# 7_Segment_master.net
KiCad netlist of a schematic drawn in EAGLE
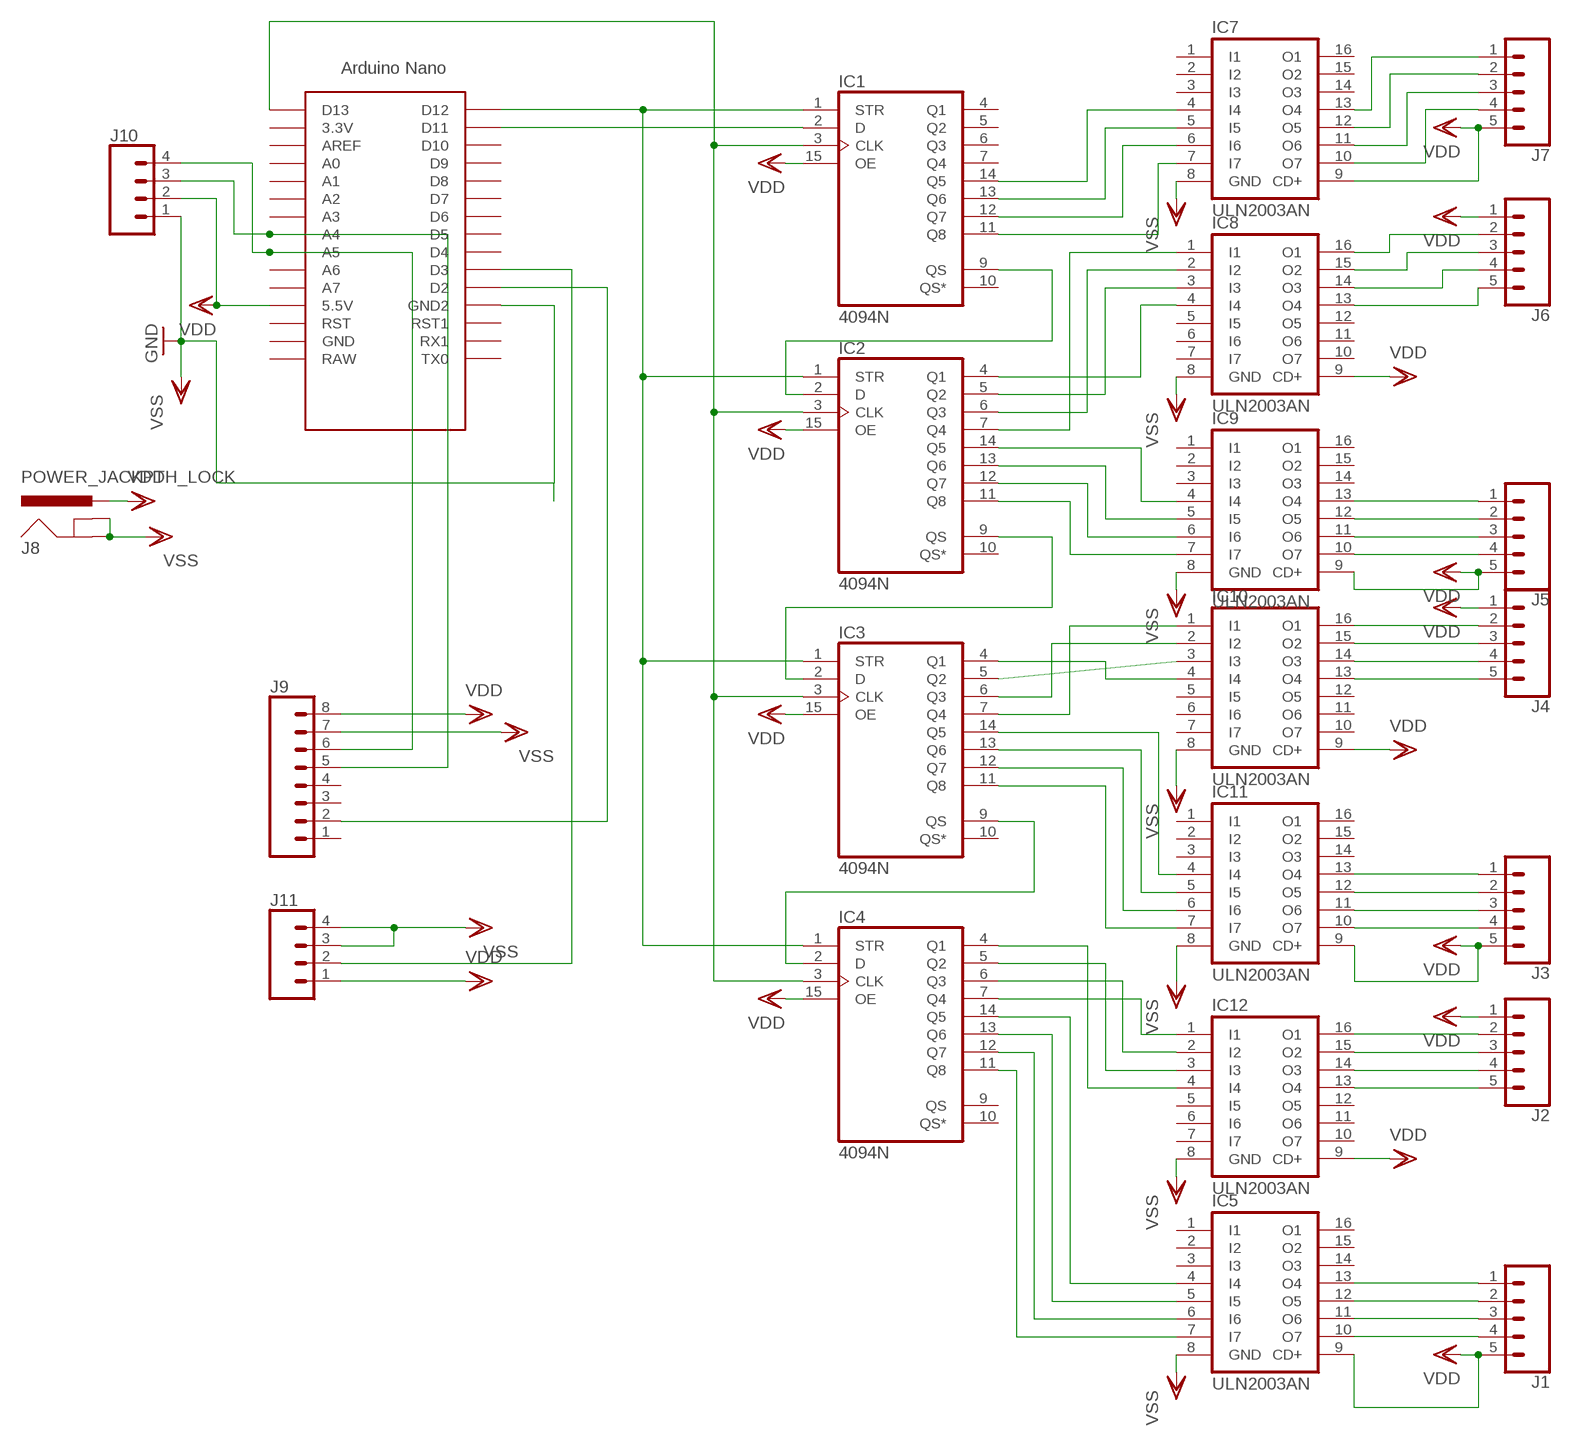
[diagram p0: schematic, sheet 1]

(export (version "E")
  (design (tool "Eeschema 10.0.6"))
  (components
    (comp (ref "IC1")
      (value "4094N")
      (footprint "eagle-import:DIL16")
      (libsource (lib "eagle-import") (part "4094N"))
    )
    (comp (ref "IC2")
      (value "4094N")
      (footprint "eagle-import:DIL16")
      (libsource (lib "eagle-import") (part "4094N"))
    )
    (comp (ref "IC3")
      (value "4094N")
      (footprint "eagle-import:DIL16")
      (libsource (lib "eagle-import") (part "4094N"))
    )
    (comp (ref "IC4")
      (value "4094N")
      (footprint "eagle-import:DIL16")
      (libsource (lib "eagle-import") (part "4094N"))
    )
    (comp (ref "IC5")
      (value "ULN2003AN")
      (footprint "eagle-import:DIL16")
      (libsource (lib "eagle-import") (part "ULN2003AN"))
    )
    (comp (ref "IC7")
      (value "ULN2003AN")
      (footprint "eagle-import:DIL16")
      (libsource (lib "eagle-import") (part "ULN2003AN"))
    )
    (comp (ref "IC8")
      (value "ULN2003AN")
      (footprint "eagle-import:DIL16")
      (libsource (lib "eagle-import") (part "ULN2003AN"))
    )
    (comp (ref "IC9")
      (value "ULN2003AN")
      (footprint "eagle-import:DIL16")
      (libsource (lib "eagle-import") (part "ULN2003AN"))
    )
    (comp (ref "IC10")
      (value "ULN2003AN")
      (footprint "eagle-import:DIL16")
      (libsource (lib "eagle-import") (part "ULN2003AN"))
    )
    (comp (ref "IC11")
      (value "ULN2003AN")
      (footprint "eagle-import:DIL16")
      (libsource (lib "eagle-import") (part "ULN2003AN"))
    )
    (comp (ref "IC12")
      (value "ULN2003AN")
      (footprint "eagle-import:DIL16")
      (libsource (lib "eagle-import") (part "ULN2003AN"))
    )
    (comp (ref "J1")
      (value "CONN_05LOCK_LONGPADS")
      (footprint "eagle-import:1X05_LOCK_LONGPADS")
      (libsource (lib "eagle-import") (part "CONN_05LOCK_LONGPADS"))
    )
    (comp (ref "J2")
      (value "CONN_05LOCK_LONGPADS")
      (footprint "eagle-import:1X05_LOCK_LONGPADS")
      (libsource (lib "eagle-import") (part "CONN_05LOCK_LONGPADS"))
    )
    (comp (ref "J3")
      (value "CONN_05LOCK_LONGPADS")
      (footprint "eagle-import:1X05_LOCK_LONGPADS")
      (libsource (lib "eagle-import") (part "CONN_05LOCK_LONGPADS"))
    )
    (comp (ref "J4")
      (value "CONN_05LOCK_LONGPADS")
      (footprint "eagle-import:1X05_LOCK_LONGPADS")
      (libsource (lib "eagle-import") (part "CONN_05LOCK_LONGPADS"))
    )
    (comp (ref "J5")
      (value "CONN_05LOCK_LONGPADS")
      (footprint "eagle-import:1X05_LOCK_LONGPADS")
      (libsource (lib "eagle-import") (part "CONN_05LOCK_LONGPADS"))
    )
    (comp (ref "J6")
      (value "CONN_05LOCK_LONGPADS")
      (footprint "eagle-import:1X05_LOCK_LONGPADS")
      (libsource (lib "eagle-import") (part "CONN_05LOCK_LONGPADS"))
    )
    (comp (ref "J7")
      (value "CONN_05LOCK_LONGPADS")
      (footprint "eagle-import:1X05_LOCK_LONGPADS")
      (libsource (lib "eagle-import") (part "CONN_05LOCK_LONGPADS"))
    )
    (comp (ref "J8")
      (value "POWER_JACKPTH_LOCK")
      (footprint "eagle-import:POWER_JACK_PTH_LOCK")
      (libsource (lib "eagle-import") (part "POWER_JACKPTH_LOCK"))
    )
    (comp (ref "J9")
      (value "CONN_08LOCK_LONGPADS")
      (footprint "eagle-import:1X08_LOCK_LONGPADS")
      (libsource (lib "eagle-import") (part "CONN_08LOCK_LONGPADS"))
    )
    (comp (ref "J10")
      (value "CONN_04")
      (footprint "eagle-import:SCREWTERMINAL-5MM-4")
      (libsource (lib "eagle-import") (part "CONN_04"))
    )
    (comp (ref "J11")
      (value "CONN_04LOCK_LONGPADS")
      (footprint "eagle-import:1X04_LOCK_LONGPADS")
      (libsource (lib "eagle-import") (part "CONN_04LOCK_LONGPADS"))
    )
    (comp (ref "U$1")
      (value "NANO")
      (footprint "eagle-import:NANO")
      (libsource (lib "eagle-import") (part "NANO"))
    )
  )
  (nets
    (net (code "1") (name "GND") (class "Default")
      (node (ref "IC10") (pin "8") (pinfunction "GND_8") (pintype "power_in"))
      (node (ref "IC11") (pin "8") (pinfunction "GND_8") (pintype "power_in"))
      (node (ref "IC12") (pin "8") (pinfunction "GND_8") (pintype "power_in"))
      (node (ref "IC5") (pin "8") (pinfunction "GND_8") (pintype "power_in"))
      (node (ref "IC7") (pin "8") (pinfunction "GND_8") (pintype "power_in"))
      (node (ref "IC8") (pin "8") (pinfunction "GND_8") (pintype "power_in"))
      (node (ref "IC9") (pin "8") (pinfunction "GND_8") (pintype "power_in"))
      (node (ref "J10") (pin "1") (pinfunction "1_1") (pintype "passive"))
      (node (ref "J11") (pin "3") (pinfunction "3_3") (pintype "passive"))
      (node (ref "J11") (pin "4") (pinfunction "4_4") (pintype "passive"))
      (node (ref "J8") (pin "GND") (pinfunction "GND_GND") (pintype "bidirectional"))
      (node (ref "J8") (pin "GNDBREAK") (pinfunction "GNDBREAK_GNDBREAK") (pintype "bidirectional"))
      (node (ref "J9") (pin "7") (pinfunction "7_7") (pintype "passive"))
      (node (ref "U$1") (pin "GND1") (pinfunction "GND2_GND1") (pintype "bidirectional"))
    )
    (net (code "2") (name "Net-(IC1A-CLK)") (class "Default")
      (node (ref "IC1") (pin "3") (pinfunction "CLK_3") (pintype "input"))
      (node (ref "IC2") (pin "3") (pinfunction "CLK_3") (pintype "input"))
      (node (ref "IC3") (pin "3") (pinfunction "CLK_3") (pintype "input"))
      (node (ref "IC4") (pin "3") (pinfunction "CLK_3") (pintype "input"))
      (node (ref "U$1") (pin "D13") (pinfunction "D13_D13") (pintype "bidirectional"))
    )
    (net (code "3") (name "Net-(IC1A-D)") (class "Default")
      (node (ref "IC1") (pin "2") (pinfunction "D_2") (pintype "input"))
      (node (ref "U$1") (pin "D11") (pinfunction "D11_D11") (pintype "bidirectional"))
    )
    (net (code "4") (name "Net-(IC1A-Q5)") (class "Default")
      (node (ref "IC1") (pin "14") (pinfunction "Q5_14") (pintype "output"))
      (node (ref "IC7") (pin "4") (pinfunction "I4_4") (pintype "input"))
    )
    (net (code "5") (name "Net-(IC1A-Q6)") (class "Default")
      (node (ref "IC1") (pin "13") (pinfunction "Q6_13") (pintype "output"))
      (node (ref "IC7") (pin "5") (pinfunction "I5_5") (pintype "input"))
    )
    (net (code "6") (name "Net-(IC1A-Q7)") (class "Default")
      (node (ref "IC1") (pin "12") (pinfunction "Q7_12") (pintype "output"))
      (node (ref "IC7") (pin "6") (pinfunction "I6_6") (pintype "input"))
    )
    (net (code "7") (name "Net-(IC1A-Q8)") (class "Default")
      (node (ref "IC1") (pin "11") (pinfunction "Q8_11") (pintype "output"))
      (node (ref "IC7") (pin "7") (pinfunction "I7_7") (pintype "input"))
    )
    (net (code "8") (name "Net-(IC1A-QS)") (class "Default")
      (node (ref "IC1") (pin "9") (pinfunction "QS_9") (pintype "output"))
      (node (ref "IC2") (pin "2") (pinfunction "D_2") (pintype "input"))
    )
    (net (code "9") (name "Net-(IC1A-STR)") (class "Default")
      (node (ref "IC1") (pin "1") (pinfunction "STR_1") (pintype "input"))
      (node (ref "IC2") (pin "1") (pinfunction "STR_1") (pintype "input"))
      (node (ref "IC3") (pin "1") (pinfunction "STR_1") (pintype "input"))
      (node (ref "IC4") (pin "1") (pinfunction "STR_1") (pintype "input"))
      (node (ref "U$1") (pin "D12") (pinfunction "D12_D12") (pintype "bidirectional"))
    )
    (net (code "10") (name "Net-(IC2A-Q1)") (class "Default")
      (node (ref "IC2") (pin "4") (pinfunction "Q1_4") (pintype "output"))
      (node (ref "IC8") (pin "4") (pinfunction "I4_4") (pintype "input"))
    )
    (net (code "11") (name "Net-(IC2A-Q2)") (class "Default")
      (node (ref "IC2") (pin "5") (pinfunction "Q2_5") (pintype "output"))
      (node (ref "IC8") (pin "3") (pinfunction "I3_3") (pintype "input"))
    )
    (net (code "12") (name "Net-(IC2A-Q3)") (class "Default")
      (node (ref "IC2") (pin "6") (pinfunction "Q3_6") (pintype "output"))
      (node (ref "IC8") (pin "2") (pinfunction "I2_2") (pintype "input"))
    )
    (net (code "13") (name "Net-(IC2A-Q4)") (class "Default")
      (node (ref "IC2") (pin "7") (pinfunction "Q4_7") (pintype "output"))
      (node (ref "IC8") (pin "1") (pinfunction "I1_1") (pintype "input"))
    )
    (net (code "14") (name "Net-(IC2A-Q5)") (class "Default")
      (node (ref "IC2") (pin "14") (pinfunction "Q5_14") (pintype "output"))
      (node (ref "IC9") (pin "4") (pinfunction "I4_4") (pintype "input"))
    )
    (net (code "15") (name "Net-(IC2A-Q6)") (class "Default")
      (node (ref "IC2") (pin "13") (pinfunction "Q6_13") (pintype "output"))
      (node (ref "IC9") (pin "5") (pinfunction "I5_5") (pintype "input"))
    )
    (net (code "16") (name "Net-(IC2A-Q7)") (class "Default")
      (node (ref "IC2") (pin "12") (pinfunction "Q7_12") (pintype "output"))
      (node (ref "IC9") (pin "6") (pinfunction "I6_6") (pintype "input"))
    )
    (net (code "17") (name "Net-(IC2A-Q8)") (class "Default")
      (node (ref "IC2") (pin "11") (pinfunction "Q8_11") (pintype "output"))
      (node (ref "IC9") (pin "7") (pinfunction "I7_7") (pintype "input"))
    )
    (net (code "18") (name "Net-(IC2A-QS)") (class "Default")
      (node (ref "IC2") (pin "9") (pinfunction "QS_9") (pintype "output"))
      (node (ref "IC3") (pin "2") (pinfunction "D_2") (pintype "input"))
    )
    (net (code "19") (name "Net-(IC3A-QS)") (class "Default")
      (node (ref "IC3") (pin "9") (pinfunction "QS_9") (pintype "output"))
      (node (ref "IC4") (pin "2") (pinfunction "D_2") (pintype "input"))
    )
    (net (code "20") (name "Net-(IC4A-Q5)") (class "Default")
      (node (ref "IC4") (pin "14") (pinfunction "Q5_14") (pintype "output"))
      (node (ref "IC5") (pin "4") (pinfunction "I4_4") (pintype "input"))
    )
    (net (code "21") (name "Net-(IC4A-Q6)") (class "Default")
      (node (ref "IC4") (pin "13") (pinfunction "Q6_13") (pintype "output"))
      (node (ref "IC5") (pin "5") (pinfunction "I5_5") (pintype "input"))
    )
    (net (code "22") (name "Net-(IC4A-Q7)") (class "Default")
      (node (ref "IC4") (pin "12") (pinfunction "Q7_12") (pintype "output"))
      (node (ref "IC5") (pin "6") (pinfunction "I6_6") (pintype "input"))
    )
    (net (code "23") (name "Net-(IC4A-Q8)") (class "Default")
      (node (ref "IC4") (pin "11") (pinfunction "Q8_11") (pintype "output"))
      (node (ref "IC5") (pin "7") (pinfunction "I7_7") (pintype "input"))
    )
    (net (code "24") (name "Net-(IC5-O4)") (class "Default")
      (node (ref "IC5") (pin "13") (pinfunction "O4_13") (pintype "open_collector"))
      (node (ref "J1") (pin "1") (pinfunction "1_1") (pintype "passive"))
    )
    (net (code "25") (name "Net-(IC5-O5)") (class "Default")
      (node (ref "IC5") (pin "12") (pinfunction "O5_12") (pintype "open_collector"))
      (node (ref "J1") (pin "2") (pinfunction "2_2") (pintype "passive"))
    )
    (net (code "26") (name "Net-(IC5-O6)") (class "Default")
      (node (ref "IC5") (pin "11") (pinfunction "O6_11") (pintype "open_collector"))
      (node (ref "J1") (pin "3") (pinfunction "3_3") (pintype "passive"))
    )
    (net (code "27") (name "Net-(IC5-O7)") (class "Default")
      (node (ref "IC5") (pin "10") (pinfunction "O7_10") (pintype "open_collector"))
      (node (ref "J1") (pin "4") (pinfunction "4_4") (pintype "passive"))
    )
    (net (code "28") (name "Net-(IC7-O4)") (class "Default")
      (node (ref "IC7") (pin "13") (pinfunction "O4_13") (pintype "open_collector"))
      (node (ref "J7") (pin "1") (pinfunction "1_1") (pintype "passive"))
    )
    (net (code "29") (name "Net-(IC7-O5)") (class "Default")
      (node (ref "IC7") (pin "12") (pinfunction "O5_12") (pintype "open_collector"))
      (node (ref "J7") (pin "2") (pinfunction "2_2") (pintype "passive"))
    )
    (net (code "30") (name "Net-(IC7-O6)") (class "Default")
      (node (ref "IC7") (pin "11") (pinfunction "O6_11") (pintype "open_collector"))
      (node (ref "J7") (pin "3") (pinfunction "3_3") (pintype "passive"))
    )
    (net (code "31") (name "Net-(IC7-O7)") (class "Default")
      (node (ref "IC7") (pin "10") (pinfunction "O7_10") (pintype "open_collector"))
      (node (ref "J7") (pin "4") (pinfunction "4_4") (pintype "passive"))
    )
    (net (code "32") (name "Net-(IC8-O1)") (class "Default")
      (node (ref "IC8") (pin "16") (pinfunction "O1_16") (pintype "open_collector"))
      (node (ref "J6") (pin "2") (pinfunction "2_2") (pintype "passive"))
    )
    (net (code "33") (name "Net-(IC8-O2)") (class "Default")
      (node (ref "IC8") (pin "15") (pinfunction "O2_15") (pintype "open_collector"))
      (node (ref "J6") (pin "3") (pinfunction "3_3") (pintype "passive"))
    )
    (net (code "34") (name "Net-(IC8-O3)") (class "Default")
      (node (ref "IC8") (pin "14") (pinfunction "O3_14") (pintype "open_collector"))
      (node (ref "J6") (pin "4") (pinfunction "4_4") (pintype "passive"))
    )
    (net (code "35") (name "Net-(IC8-O4)") (class "Default")
      (node (ref "IC8") (pin "13") (pinfunction "O4_13") (pintype "open_collector"))
      (node (ref "J6") (pin "5") (pinfunction "5_5") (pintype "passive"))
    )
    (net (code "36") (name "Net-(IC9-O4)") (class "Default")
      (node (ref "IC9") (pin "13") (pinfunction "O4_13") (pintype "open_collector"))
      (node (ref "J5") (pin "1") (pinfunction "1_1") (pintype "passive"))
    )
    (net (code "37") (name "Net-(IC9-O5)") (class "Default")
      (node (ref "IC9") (pin "12") (pinfunction "O5_12") (pintype "open_collector"))
      (node (ref "J5") (pin "2") (pinfunction "2_2") (pintype "passive"))
    )
    (net (code "38") (name "Net-(IC9-O6)") (class "Default")
      (node (ref "IC9") (pin "11") (pinfunction "O6_11") (pintype "open_collector"))
      (node (ref "J5") (pin "3") (pinfunction "3_3") (pintype "passive"))
    )
    (net (code "39") (name "Net-(IC9-O7)") (class "Default")
      (node (ref "IC9") (pin "10") (pinfunction "O7_10") (pintype "open_collector"))
      (node (ref "J5") (pin "4") (pinfunction "4_4") (pintype "passive"))
    )
    (net (code "40") (name "Net-(IC10-I1)") (class "Default")
      (node (ref "IC10") (pin "1") (pinfunction "I1_1") (pintype "input"))
      (node (ref "IC3") (pin "7") (pinfunction "Q4_7") (pintype "output"))
    )
    (net (code "41") (name "Net-(IC10-I2)") (class "Default")
      (node (ref "IC10") (pin "2") (pinfunction "I2_2") (pintype "input"))
      (node (ref "IC3") (pin "6") (pinfunction "Q3_6") (pintype "output"))
    )
    (net (code "42") (name "Net-(IC10-I3)") (class "Default")
      (node (ref "IC10") (pin "3") (pinfunction "I3_3") (pintype "input"))
      (node (ref "IC3") (pin "5") (pinfunction "Q2_5") (pintype "output"))
    )
    (net (code "43") (name "Net-(IC10-I4)") (class "Default")
      (node (ref "IC10") (pin "4") (pinfunction "I4_4") (pintype "input"))
      (node (ref "IC3") (pin "4") (pinfunction "Q1_4") (pintype "output"))
    )
    (net (code "44") (name "Net-(IC10-O1)") (class "Default")
      (node (ref "IC10") (pin "16") (pinfunction "O1_16") (pintype "open_collector"))
      (node (ref "J4") (pin "2") (pinfunction "2_2") (pintype "passive"))
    )
    (net (code "45") (name "Net-(IC10-O2)") (class "Default")
      (node (ref "IC10") (pin "15") (pinfunction "O2_15") (pintype "open_collector"))
      (node (ref "J4") (pin "3") (pinfunction "3_3") (pintype "passive"))
    )
    (net (code "46") (name "Net-(IC10-O3)") (class "Default")
      (node (ref "IC10") (pin "14") (pinfunction "O3_14") (pintype "open_collector"))
      (node (ref "J4") (pin "4") (pinfunction "4_4") (pintype "passive"))
    )
    (net (code "47") (name "Net-(IC10-O4)") (class "Default")
      (node (ref "IC10") (pin "13") (pinfunction "O4_13") (pintype "open_collector"))
      (node (ref "J4") (pin "5") (pinfunction "5_5") (pintype "passive"))
    )
    (net (code "48") (name "Net-(IC11-I4)") (class "Default")
      (node (ref "IC11") (pin "4") (pinfunction "I4_4") (pintype "input"))
      (node (ref "IC3") (pin "14") (pinfunction "Q5_14") (pintype "output"))
    )
    (net (code "49") (name "Net-(IC11-I5)") (class "Default")
      (node (ref "IC11") (pin "5") (pinfunction "I5_5") (pintype "input"))
      (node (ref "IC3") (pin "13") (pinfunction "Q6_13") (pintype "output"))
    )
    (net (code "50") (name "Net-(IC11-I6)") (class "Default")
      (node (ref "IC11") (pin "6") (pinfunction "I6_6") (pintype "input"))
      (node (ref "IC3") (pin "12") (pinfunction "Q7_12") (pintype "output"))
    )
    (net (code "51") (name "Net-(IC11-I7)") (class "Default")
      (node (ref "IC11") (pin "7") (pinfunction "I7_7") (pintype "input"))
      (node (ref "IC3") (pin "11") (pinfunction "Q8_11") (pintype "output"))
    )
    (net (code "52") (name "Net-(IC11-O4)") (class "Default")
      (node (ref "IC11") (pin "13") (pinfunction "O4_13") (pintype "open_collector"))
      (node (ref "J3") (pin "1") (pinfunction "1_1") (pintype "passive"))
    )
    (net (code "53") (name "Net-(IC11-O5)") (class "Default")
      (node (ref "IC11") (pin "12") (pinfunction "O5_12") (pintype "open_collector"))
      (node (ref "J3") (pin "2") (pinfunction "2_2") (pintype "passive"))
    )
    (net (code "54") (name "Net-(IC11-O6)") (class "Default")
      (node (ref "IC11") (pin "11") (pinfunction "O6_11") (pintype "open_collector"))
      (node (ref "J3") (pin "3") (pinfunction "3_3") (pintype "passive"))
    )
    (net (code "55") (name "Net-(IC11-O7)") (class "Default")
      (node (ref "IC11") (pin "10") (pinfunction "O7_10") (pintype "open_collector"))
      (node (ref "J3") (pin "4") (pinfunction "4_4") (pintype "passive"))
    )
    (net (code "56") (name "Net-(IC12-I1)") (class "Default")
      (node (ref "IC12") (pin "1") (pinfunction "I1_1") (pintype "input"))
      (node (ref "IC4") (pin "7") (pinfunction "Q4_7") (pintype "output"))
    )
    (net (code "57") (name "Net-(IC12-I2)") (class "Default")
      (node (ref "IC12") (pin "2") (pinfunction "I2_2") (pintype "input"))
      (node (ref "IC4") (pin "6") (pinfunction "Q3_6") (pintype "output"))
    )
    (net (code "58") (name "Net-(IC12-I3)") (class "Default")
      (node (ref "IC12") (pin "3") (pinfunction "I3_3") (pintype "input"))
      (node (ref "IC4") (pin "5") (pinfunction "Q2_5") (pintype "output"))
    )
    (net (code "59") (name "Net-(IC12-I4)") (class "Default")
      (node (ref "IC12") (pin "4") (pinfunction "I4_4") (pintype "input"))
      (node (ref "IC4") (pin "4") (pinfunction "Q1_4") (pintype "output"))
    )
    (net (code "60") (name "Net-(IC12-O1)") (class "Default")
      (node (ref "IC12") (pin "16") (pinfunction "O1_16") (pintype "open_collector"))
      (node (ref "J2") (pin "2") (pinfunction "2_2") (pintype "passive"))
    )
    (net (code "61") (name "Net-(IC12-O2)") (class "Default")
      (node (ref "IC12") (pin "15") (pinfunction "O2_15") (pintype "open_collector"))
      (node (ref "J2") (pin "3") (pinfunction "3_3") (pintype "passive"))
    )
    (net (code "62") (name "Net-(IC12-O3)") (class "Default")
      (node (ref "IC12") (pin "14") (pinfunction "O3_14") (pintype "open_collector"))
      (node (ref "J2") (pin "4") (pinfunction "4_4") (pintype "passive"))
    )
    (net (code "63") (name "Net-(IC12-O4)") (class "Default")
      (node (ref "IC12") (pin "13") (pinfunction "O4_13") (pintype "open_collector"))
      (node (ref "J2") (pin "5") (pinfunction "5_5") (pintype "passive"))
    )
    (net (code "64") (name "Net-(J9-Pad2)") (class "Default")
      (node (ref "J9") (pin "2") (pinfunction "2_2") (pintype "passive"))
      (node (ref "U$1") (pin "D2") (pinfunction "D2_D2") (pintype "bidirectional"))
    )
    (net (code "65") (name "Net-(J10-Pad3)") (class "Default")
      (node (ref "J10") (pin "3") (pinfunction "3_3") (pintype "passive"))
      (node (ref "J9") (pin "5") (pinfunction "5_5") (pintype "passive"))
      (node (ref "U$1") (pin "A4") (pinfunction "A4_A4") (pintype "bidirectional"))
    )
    (net (code "66") (name "Net-(J10-Pad4)") (class "Default")
      (node (ref "J10") (pin "4") (pinfunction "4_4") (pintype "passive"))
      (node (ref "J9") (pin "6") (pinfunction "6_6") (pintype "passive"))
      (node (ref "U$1") (pin "A5") (pinfunction "A5_A5") (pintype "bidirectional"))
    )
    (net (code "67") (name "Net-(J11-Pad2)") (class "Default")
      (node (ref "J11") (pin "2") (pinfunction "2_2") (pintype "passive"))
      (node (ref "U$1") (pin "D3") (pinfunction "D3_D3") (pintype "bidirectional"))
    )
    (net (code "68") (name "VDD") (class "Default")
      (node (ref "IC1") (pin "15") (pinfunction "OE_15") (pintype "input"))
      (node (ref "IC10") (pin "9") (pinfunction "CD+_9") (pintype "passive"))
      (node (ref "IC11") (pin "9") (pinfunction "CD+_9") (pintype "passive"))
      (node (ref "IC12") (pin "9") (pinfunction "CD+_9") (pintype "passive"))
      (node (ref "IC2") (pin "15") (pinfunction "OE_15") (pintype "input"))
      (node (ref "IC3") (pin "15") (pinfunction "OE_15") (pintype "input"))
      (node (ref "IC4") (pin "15") (pinfunction "OE_15") (pintype "input"))
      (node (ref "IC5") (pin "9") (pinfunction "CD+_9") (pintype "passive"))
      (node (ref "IC7") (pin "9") (pinfunction "CD+_9") (pintype "passive"))
      (node (ref "IC8") (pin "9") (pinfunction "CD+_9") (pintype "passive"))
      (node (ref "IC9") (pin "9") (pinfunction "CD+_9") (pintype "passive"))
      (node (ref "J1") (pin "5") (pinfunction "5_5") (pintype "passive"))
      (node (ref "J10") (pin "2") (pinfunction "2_2") (pintype "passive"))
      (node (ref "J11") (pin "1") (pinfunction "1_1") (pintype "passive"))
      (node (ref "J2") (pin "1") (pinfunction "1_1") (pintype "passive"))
      (node (ref "J3") (pin "5") (pinfunction "5_5") (pintype "passive"))
      (node (ref "J4") (pin "1") (pinfunction "1_1") (pintype "passive"))
      (node (ref "J5") (pin "5") (pinfunction "5_5") (pintype "passive"))
      (node (ref "J6") (pin "1") (pinfunction "1_1") (pintype "passive"))
      (node (ref "J7") (pin "5") (pinfunction "5_5") (pintype "passive"))
      (node (ref "J8") (pin "PWR") (pinfunction "PWR_PWR") (pintype "bidirectional"))
      (node (ref "J9") (pin "8") (pinfunction "8_8") (pintype "passive"))
      (node (ref "U$1") (pin "5V") (pinfunction "5.5V_5V") (pintype "bidirectional"))
    )
    (net (code "69") (name "unconnected-(IC1A-Q1-Pad4)") (class "Default")
      (node (ref "IC1") (pin "4") (pinfunction "Q1_4") (pintype "output"))
    )
    (net (code "70") (name "unconnected-(IC1A-Q2-Pad5)") (class "Default")
      (node (ref "IC1") (pin "5") (pinfunction "Q2_5") (pintype "output"))
    )
    (net (code "71") (name "unconnected-(IC1A-Q3-Pad6)") (class "Default")
      (node (ref "IC1") (pin "6") (pinfunction "Q3_6") (pintype "output"))
    )
    (net (code "72") (name "unconnected-(IC1A-Q4-Pad7)") (class "Default")
      (node (ref "IC1") (pin "7") (pinfunction "Q4_7") (pintype "output"))
    )
    (net (code "73") (name "unconnected-(IC1A-QS*-Pad10)") (class "Default")
      (node (ref "IC1") (pin "10") (pinfunction "QS*_10") (pintype "output"))
    )
    (net (code "74") (name "unconnected-(IC2A-QS*-Pad10)") (class "Default")
      (node (ref "IC2") (pin "10") (pinfunction "QS*_10") (pintype "output"))
    )
    (net (code "75") (name "unconnected-(IC3A-QS*-Pad10)") (class "Default")
      (node (ref "IC3") (pin "10") (pinfunction "QS*_10") (pintype "output"))
    )
    (net (code "76") (name "unconnected-(IC4A-QS*-Pad10)") (class "Default")
      (node (ref "IC4") (pin "10") (pinfunction "QS*_10") (pintype "output"))
    )
    (net (code "77") (name "unconnected-(IC4A-QS-Pad9)") (class "Default")
      (node (ref "IC4") (pin "9") (pinfunction "QS_9") (pintype "output"))
    )
    (net (code "78") (name "unconnected-(IC5-I1-Pad1)") (class "Default")
      (node (ref "IC5") (pin "1") (pinfunction "I1_1") (pintype "input"))
    )
    (net (code "79") (name "unconnected-(IC5-I2-Pad2)") (class "Default")
      (node (ref "IC5") (pin "2") (pinfunction "I2_2") (pintype "input"))
    )
    (net (code "80") (name "unconnected-(IC5-I3-Pad3)") (class "Default")
      (node (ref "IC5") (pin "3") (pinfunction "I3_3") (pintype "input"))
    )
    (net (code "81") (name "unconnected-(IC5-O1-Pad16)") (class "Default")
      (node (ref "IC5") (pin "16") (pinfunction "O1_16") (pintype "open_collector"))
    )
    (net (code "82") (name "unconnected-(IC5-O2-Pad15)") (class "Default")
      (node (ref "IC5") (pin "15") (pinfunction "O2_15") (pintype "open_collector"))
    )
    (net (code "83") (name "unconnected-(IC5-O3-Pad14)") (class "Default")
      (node (ref "IC5") (pin "14") (pinfunction "O3_14") (pintype "open_collector"))
    )
    (net (code "84") (name "unconnected-(IC7-I1-Pad1)") (class "Default")
      (node (ref "IC7") (pin "1") (pinfunction "I1_1") (pintype "input"))
    )
    (net (code "85") (name "unconnected-(IC7-I2-Pad2)") (class "Default")
      (node (ref "IC7") (pin "2") (pinfunction "I2_2") (pintype "input"))
    )
    (net (code "86") (name "unconnected-(IC7-I3-Pad3)") (class "Default")
      (node (ref "IC7") (pin "3") (pinfunction "I3_3") (pintype "input"))
    )
    (net (code "87") (name "unconnected-(IC7-O1-Pad16)") (class "Default")
      (node (ref "IC7") (pin "16") (pinfunction "O1_16") (pintype "open_collector"))
    )
    (net (code "88") (name "unconnected-(IC7-O2-Pad15)") (class "Default")
      (node (ref "IC7") (pin "15") (pinfunction "O2_15") (pintype "open_collector"))
    )
    (net (code "89") (name "unconnected-(IC7-O3-Pad14)") (class "Default")
      (node (ref "IC7") (pin "14") (pinfunction "O3_14") (pintype "open_collector"))
    )
    (net (code "90") (name "unconnected-(IC8-I5-Pad5)") (class "Default")
      (node (ref "IC8") (pin "5") (pinfunction "I5_5") (pintype "input"))
    )
    (net (code "91") (name "unconnected-(IC8-I6-Pad6)") (class "Default")
      (node (ref "IC8") (pin "6") (pinfunction "I6_6") (pintype "input"))
    )
    (net (code "92") (name "unconnected-(IC8-I7-Pad7)") (class "Default")
      (node (ref "IC8") (pin "7") (pinfunction "I7_7") (pintype "input"))
    )
    (net (code "93") (name "unconnected-(IC8-O5-Pad12)") (class "Default")
      (node (ref "IC8") (pin "12") (pinfunction "O5_12") (pintype "open_collector"))
    )
    (net (code "94") (name "unconnected-(IC8-O6-Pad11)") (class "Default")
      (node (ref "IC8") (pin "11") (pinfunction "O6_11") (pintype "open_collector"))
    )
    (net (code "95") (name "unconnected-(IC8-O7-Pad10)") (class "Default")
      (node (ref "IC8") (pin "10") (pinfunction "O7_10") (pintype "open_collector"))
    )
    (net (code "96") (name "unconnected-(IC9-I1-Pad1)") (class "Default")
      (node (ref "IC9") (pin "1") (pinfunction "I1_1") (pintype "input"))
    )
    (net (code "97") (name "unconnected-(IC9-I2-Pad2)") (class "Default")
      (node (ref "IC9") (pin "2") (pinfunction "I2_2") (pintype "input"))
    )
    (net (code "98") (name "unconnected-(IC9-I3-Pad3)") (class "Default")
      (node (ref "IC9") (pin "3") (pinfunction "I3_3") (pintype "input"))
    )
    (net (code "99") (name "unconnected-(IC9-O1-Pad16)") (class "Default")
      (node (ref "IC9") (pin "16") (pinfunction "O1_16") (pintype "open_collector"))
    )
    (net (code "100") (name "unconnected-(IC9-O2-Pad15)") (class "Default")
      (node (ref "IC9") (pin "15") (pinfunction "O2_15") (pintype "open_collector"))
    )
    (net (code "101") (name "unconnected-(IC9-O3-Pad14)") (class "Default")
      (node (ref "IC9") (pin "14") (pinfunction "O3_14") (pintype "open_collector"))
    )
    (net (code "102") (name "unconnected-(IC10-I5-Pad5)") (class "Default")
      (node (ref "IC10") (pin "5") (pinfunction "I5_5") (pintype "input"))
    )
    (net (code "103") (name "unconnected-(IC10-I6-Pad6)") (class "Default")
      (node (ref "IC10") (pin "6") (pinfunction "I6_6") (pintype "input"))
    )
    (net (code "104") (name "unconnected-(IC10-I7-Pad7)") (class "Default")
      (node (ref "IC10") (pin "7") (pinfunction "I7_7") (pintype "input"))
    )
    (net (code "105") (name "unconnected-(IC10-O5-Pad12)") (class "Default")
      (node (ref "IC10") (pin "12") (pinfunction "O5_12") (pintype "open_collector"))
    )
    (net (code "106") (name "unconnected-(IC10-O6-Pad11)") (class "Default")
      (node (ref "IC10") (pin "11") (pinfunction "O6_11") (pintype "open_collector"))
    )
    (net (code "107") (name "unconnected-(IC10-O7-Pad10)") (class "Default")
      (node (ref "IC10") (pin "10") (pinfunction "O7_10") (pintype "open_collector"))
    )
    (net (code "108") (name "unconnected-(IC11-I1-Pad1)") (class "Default")
      (node (ref "IC11") (pin "1") (pinfunction "I1_1") (pintype "input"))
    )
    (net (code "109") (name "unconnected-(IC11-I2-Pad2)") (class "Default")
      (node (ref "IC11") (pin "2") (pinfunction "I2_2") (pintype "input"))
    )
    (net (code "110") (name "unconnected-(IC11-I3-Pad3)") (class "Default")
      (node (ref "IC11") (pin "3") (pinfunction "I3_3") (pintype "input"))
    )
    (net (code "111") (name "unconnected-(IC11-O1-Pad16)") (class "Default")
      (node (ref "IC11") (pin "16") (pinfunction "O1_16") (pintype "open_collector"))
    )
    (net (code "112") (name "unconnected-(IC11-O2-Pad15)") (class "Default")
      (node (ref "IC11") (pin "15") (pinfunction "O2_15") (pintype "open_collector"))
    )
    (net (code "113") (name "unconnected-(IC11-O3-Pad14)") (class "Default")
      (node (ref "IC11") (pin "14") (pinfunction "O3_14") (pintype "open_collector"))
    )
    (net (code "114") (name "unconnected-(IC12-I5-Pad5)") (class "Default")
      (node (ref "IC12") (pin "5") (pinfunction "I5_5") (pintype "input"))
    )
    (net (code "115") (name "unconnected-(IC12-I6-Pad6)") (class "Default")
      (node (ref "IC12") (pin "6") (pinfunction "I6_6") (pintype "input"))
    )
    (net (code "116") (name "unconnected-(IC12-I7-Pad7)") (class "Default")
      (node (ref "IC12") (pin "7") (pinfunction "I7_7") (pintype "input"))
    )
    (net (code "117") (name "unconnected-(IC12-O5-Pad12)") (class "Default")
      (node (ref "IC12") (pin "12") (pinfunction "O5_12") (pintype "open_collector"))
    )
    (net (code "118") (name "unconnected-(IC12-O6-Pad11)") (class "Default")
      (node (ref "IC12") (pin "11") (pinfunction "O6_11") (pintype "open_collector"))
    )
    (net (code "119") (name "unconnected-(IC12-O7-Pad10)") (class "Default")
      (node (ref "IC12") (pin "10") (pinfunction "O7_10") (pintype "open_collector"))
    )
    (net (code "120") (name "unconnected-(J9-Pad1)") (class "Default")
      (node (ref "J9") (pin "1") (pinfunction "1_1") (pintype "passive"))
    )
    (net (code "121") (name "unconnected-(J9-Pad3)") (class "Default")
      (node (ref "J9") (pin "3") (pinfunction "3_3") (pintype "passive"))
    )
    (net (code "122") (name "unconnected-(J9-Pad4)") (class "Default")
      (node (ref "J9") (pin "4") (pinfunction "4_4") (pintype "passive"))
    )
    (net (code "123") (name "unconnected-(U$1-Pad3.3V)") (class "Default")
      (node (ref "U$1") (pin "3.3V") (pinfunction "3.3V_3.3V") (pintype "bidirectional"))
    )
    (net (code "124") (name "unconnected-(U$1-PadA0)") (class "Default")
      (node (ref "U$1") (pin "A0") (pinfunction "A0_A0") (pintype "bidirectional"))
    )
    (net (code "125") (name "unconnected-(U$1-PadA1)") (class "Default")
      (node (ref "U$1") (pin "A1") (pinfunction "A1_A1") (pintype "bidirectional"))
    )
    (net (code "126") (name "unconnected-(U$1-PadA2)") (class "Default")
      (node (ref "U$1") (pin "A2") (pinfunction "A2_A2") (pintype "bidirectional"))
    )
    (net (code "127") (name "unconnected-(U$1-PadA3)") (class "Default")
      (node (ref "U$1") (pin "A3") (pinfunction "A3_A3") (pintype "bidirectional"))
    )
    (net (code "128") (name "unconnected-(U$1-PadA6)") (class "Default")
      (node (ref "U$1") (pin "A6") (pinfunction "A6_A6") (pintype "bidirectional"))
    )
    (net (code "129") (name "unconnected-(U$1-PadA7)") (class "Default")
      (node (ref "U$1") (pin "A7") (pinfunction "A7_A7") (pintype "bidirectional"))
    )
    (net (code "130") (name "unconnected-(U$1-PadAREF)") (class "Default")
      (node (ref "U$1") (pin "AREF") (pinfunction "AREF_AREF") (pintype "bidirectional"))
    )
    (net (code "131") (name "unconnected-(U$1-PadD4)") (class "Default")
      (node (ref "U$1") (pin "D4") (pinfunction "D4_D4") (pintype "bidirectional"))
    )
    (net (code "132") (name "unconnected-(U$1-PadD5)") (class "Default")
      (node (ref "U$1") (pin "D5") (pinfunction "D5_D5") (pintype "bidirectional"))
    )
    (net (code "133") (name "unconnected-(U$1-PadD6)") (class "Default")
      (node (ref "U$1") (pin "D6") (pinfunction "D6_D6") (pintype "bidirectional"))
    )
    (net (code "134") (name "unconnected-(U$1-PadD7)") (class "Default")
      (node (ref "U$1") (pin "D7") (pinfunction "D7_D7") (pintype "bidirectional"))
    )
    (net (code "135") (name "unconnected-(U$1-PadD8)") (class "Default")
      (node (ref "U$1") (pin "D8") (pinfunction "D8_D8") (pintype "bidirectional"))
    )
    (net (code "136") (name "unconnected-(U$1-PadD9)") (class "Default")
      (node (ref "U$1") (pin "D9") (pinfunction "D9_D9") (pintype "bidirectional"))
    )
    (net (code "137") (name "unconnected-(U$1-PadD10)") (class "Default")
      (node (ref "U$1") (pin "D10") (pinfunction "D10_D10") (pintype "bidirectional"))
    )
    (net (code "138") (name "unconnected-(U$1-PadGND)") (class "Default")
      (node (ref "U$1") (pin "GND") (pinfunction "GND_GND") (pintype "bidirectional"))
    )
    (net (code "139") (name "unconnected-(U$1-PadRAW)") (class "Default")
      (node (ref "U$1") (pin "RAW") (pinfunction "RAW_RAW") (pintype "bidirectional"))
    )
    (net (code "140") (name "unconnected-(U$1-PadRST)") (class "Default")
      (node (ref "U$1") (pin "RST") (pinfunction "RST_RST") (pintype "bidirectional"))
    )
    (net (code "141") (name "unconnected-(U$1-PadRST1)") (class "Default")
      (node (ref "U$1") (pin "RST1") (pinfunction "RST1_RST1") (pintype "bidirectional"))
    )
    (net (code "142") (name "unconnected-(U$1-PadRX1)") (class "Default")
      (node (ref "U$1") (pin "RX1") (pinfunction "RX1_RX1") (pintype "bidirectional"))
    )
    (net (code "143") (name "unconnected-(U$1-PadTX0)") (class "Default")
      (node (ref "U$1") (pin "TX0") (pinfunction "TX0_TX0") (pintype "bidirectional"))
    )
  )
)
